# 201_ConnectionPart2-Part1.net
KiCad netlist of a schematic drawn in Altium Designer
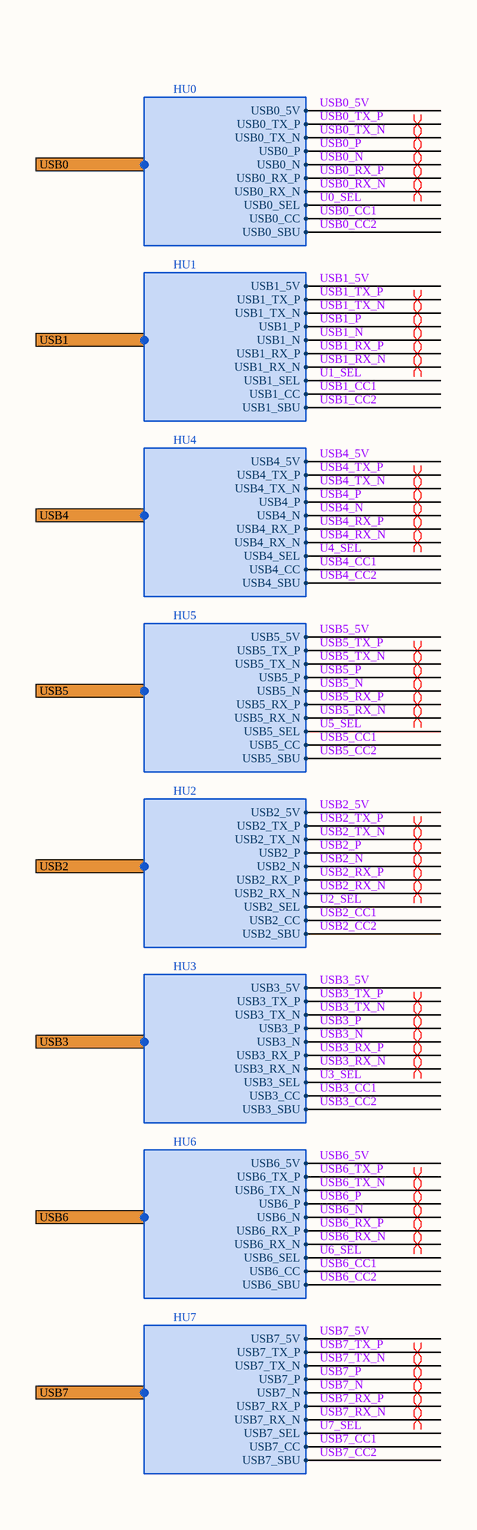
[diagram p0: 201_ConnectionPart2-Part1.SchDoc, left]
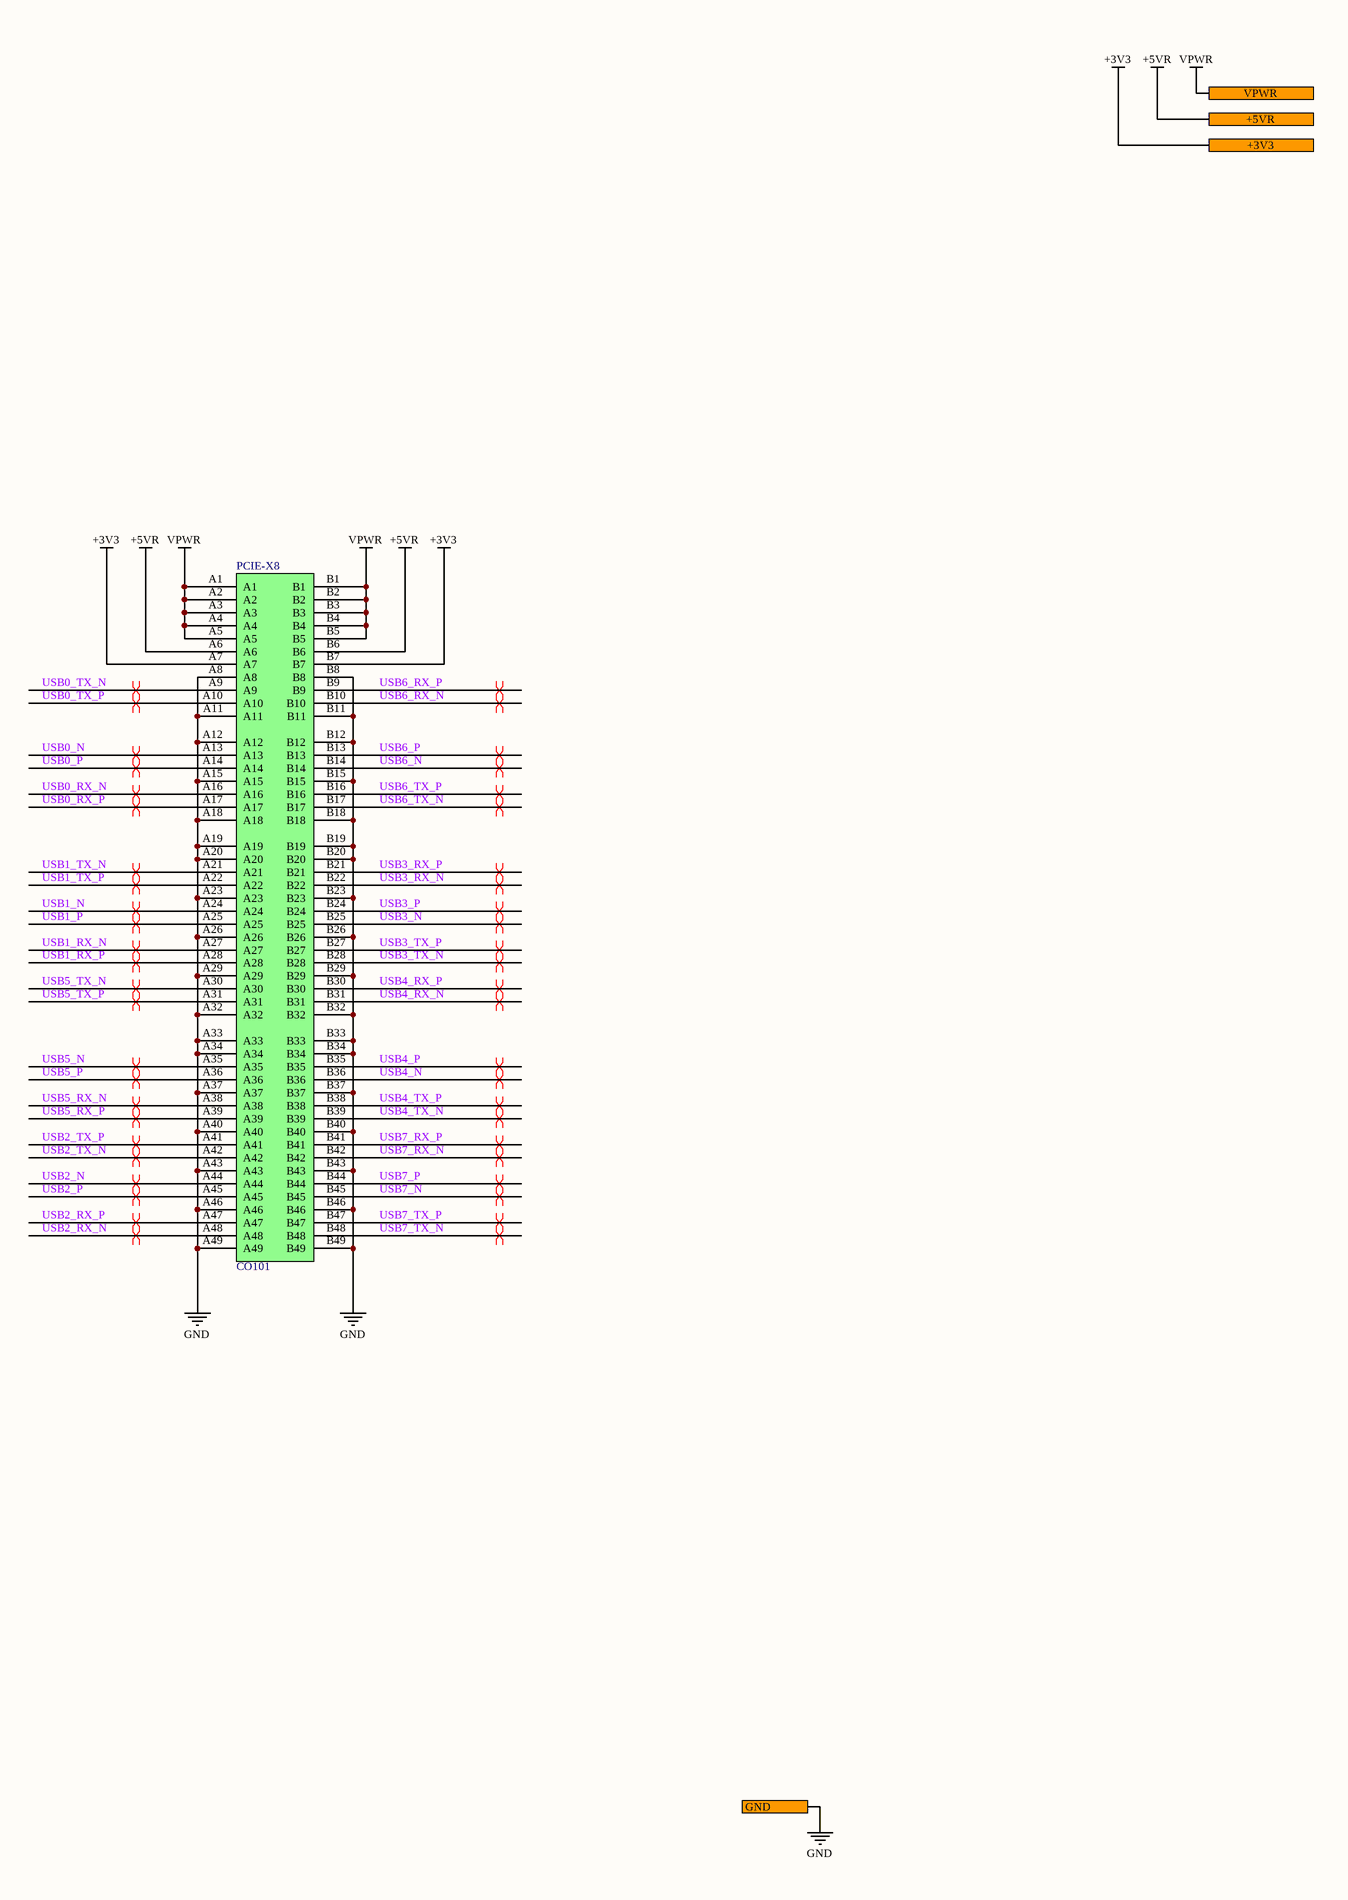
[diagram p1: 201_ConnectionPart2-Part1.SchDoc, right]

(export (version "E")
  (design (tool "Eeschema 10.0.6"))
  (components
    (comp (ref "CO101")
      (value "PCIE-X8")
      (footprint "PCIE-X8-PCB-BASIC")
      (description "PCIE GEN4-X8, Male")
      (fields (field (name "REFVAL") "PCIE-X8") (field (name "PART NUMBER") "CO0052"))
      (libsource (lib "GTS_Database") (part "PCIE-X8"))
    )
  )
  (nets
    (net (code "9") (name "+3V3") (class "Default")
      (node (ref "CO101") (pin "A7") (pinfunction "A7_A7") (pintype "passive"))
      (node (ref "CO101") (pin "B7") (pinfunction "B7_B7") (pintype "passive"))
    )
    (net (code "10") (name "+5VR") (class "Default")
      (node (ref "CO101") (pin "A6") (pinfunction "A6_A6") (pintype "passive"))
      (node (ref "CO101") (pin "B6") (pinfunction "B6_B6") (pintype "passive"))
    )
    (net (code "22") (name "/USB0_N") (class "Default")
      (node (ref "CO101") (pin "A13") (pinfunction "A13_A13") (pintype "passive"))
    )
    (net (code "23") (name "/USB0_P") (class "Default")
      (node (ref "CO101") (pin "A14") (pinfunction "A14_A14") (pintype "passive"))
    )
    (net (code "24") (name "/USB0_RX_N") (class "Default")
      (node (ref "CO101") (pin "A16") (pinfunction "A16_A16") (pintype "passive"))
    )
    (net (code "25") (name "/USB0_RX_P") (class "Default")
      (node (ref "CO101") (pin "A17") (pinfunction "A17_A17") (pintype "passive"))
    )
    (net (code "26") (name "/USB0_TX_N") (class "Default")
      (node (ref "CO101") (pin "A9") (pinfunction "A9_A9") (pintype "passive"))
    )
    (net (code "27") (name "/USB0_TX_P") (class "Default")
      (node (ref "CO101") (pin "A10") (pinfunction "A10_A10") (pintype "passive"))
    )
    (net (code "31") (name "/USB1_N") (class "Default")
      (node (ref "CO101") (pin "A24") (pinfunction "A24_A24") (pintype "passive"))
    )
    (net (code "32") (name "/USB1_P") (class "Default")
      (node (ref "CO101") (pin "A25") (pinfunction "A25_A25") (pintype "passive"))
    )
    (net (code "33") (name "/USB1_RX_N") (class "Default")
      (node (ref "CO101") (pin "A27") (pinfunction "A27_A27") (pintype "passive"))
    )
    (net (code "34") (name "/USB1_RX_P") (class "Default")
      (node (ref "CO101") (pin "A28") (pinfunction "A28_A28") (pintype "passive"))
    )
    (net (code "35") (name "/USB1_TX_N") (class "Default")
      (node (ref "CO101") (pin "A21") (pinfunction "A21_A21") (pintype "passive"))
    )
    (net (code "36") (name "/USB1_TX_P") (class "Default")
      (node (ref "CO101") (pin "A22") (pinfunction "A22_A22") (pintype "passive"))
    )
    (net (code "40") (name "/USB2_N") (class "Default")
      (node (ref "CO101") (pin "A44") (pinfunction "A44_A44") (pintype "passive"))
    )
    (net (code "41") (name "/USB2_P") (class "Default")
      (node (ref "CO101") (pin "A45") (pinfunction "A45_A45") (pintype "passive"))
    )
    (net (code "42") (name "/USB2_RX_N") (class "Default")
      (node (ref "CO101") (pin "A48") (pinfunction "A48_A48") (pintype "passive"))
    )
    (net (code "43") (name "/USB2_RX_P") (class "Default")
      (node (ref "CO101") (pin "A47") (pinfunction "A47_A47") (pintype "passive"))
    )
    (net (code "44") (name "/USB2_TX_N") (class "Default")
      (node (ref "CO101") (pin "A42") (pinfunction "A42_A42") (pintype "passive"))
    )
    (net (code "45") (name "/USB2_TX_P") (class "Default")
      (node (ref "CO101") (pin "A41") (pinfunction "A41_A41") (pintype "passive"))
    )
    (net (code "49") (name "/USB3_N") (class "Default")
      (node (ref "CO101") (pin "B25") (pinfunction "B25_B25") (pintype "passive"))
    )
    (net (code "50") (name "/USB3_P") (class "Default")
      (node (ref "CO101") (pin "B24") (pinfunction "B24_B24") (pintype "passive"))
    )
    (net (code "51") (name "/USB3_RX_N") (class "Default")
      (node (ref "CO101") (pin "B22") (pinfunction "B22_B22") (pintype "passive"))
    )
    (net (code "52") (name "/USB3_RX_P") (class "Default")
      (node (ref "CO101") (pin "B21") (pinfunction "B21_B21") (pintype "passive"))
    )
    (net (code "53") (name "/USB3_TX_N") (class "Default")
      (node (ref "CO101") (pin "B28") (pinfunction "B28_B28") (pintype "passive"))
    )
    (net (code "54") (name "/USB3_TX_P") (class "Default")
      (node (ref "CO101") (pin "B27") (pinfunction "B27_B27") (pintype "passive"))
    )
    (net (code "58") (name "/USB4_N") (class "Default")
      (node (ref "CO101") (pin "B36") (pinfunction "B36_B36") (pintype "passive"))
    )
    (net (code "59") (name "/USB4_P") (class "Default")
      (node (ref "CO101") (pin "B35") (pinfunction "B35_B35") (pintype "passive"))
    )
    (net (code "60") (name "/USB4_RX_N") (class "Default")
      (node (ref "CO101") (pin "B31") (pinfunction "B31_B31") (pintype "passive"))
    )
    (net (code "61") (name "/USB4_RX_P") (class "Default")
      (node (ref "CO101") (pin "B30") (pinfunction "B30_B30") (pintype "passive"))
    )
    (net (code "62") (name "/USB4_TX_N") (class "Default")
      (node (ref "CO101") (pin "B39") (pinfunction "B39_B39") (pintype "passive"))
    )
    (net (code "63") (name "/USB4_TX_P") (class "Default")
      (node (ref "CO101") (pin "B38") (pinfunction "B38_B38") (pintype "passive"))
    )
    (net (code "67") (name "/USB5_N") (class "Default")
      (node (ref "CO101") (pin "A35") (pinfunction "A35_A35") (pintype "passive"))
    )
    (net (code "68") (name "/USB5_P") (class "Default")
      (node (ref "CO101") (pin "A36") (pinfunction "A36_A36") (pintype "passive"))
    )
    (net (code "69") (name "/USB5_RX_N") (class "Default")
      (node (ref "CO101") (pin "A38") (pinfunction "A38_A38") (pintype "passive"))
    )
    (net (code "70") (name "/USB5_RX_P") (class "Default")
      (node (ref "CO101") (pin "A39") (pinfunction "A39_A39") (pintype "passive"))
    )
    (net (code "71") (name "/USB5_TX_N") (class "Default")
      (node (ref "CO101") (pin "A30") (pinfunction "A30_A30") (pintype "passive"))
    )
    (net (code "72") (name "/USB5_TX_P") (class "Default")
      (node (ref "CO101") (pin "A31") (pinfunction "A31_A31") (pintype "passive"))
    )
    (net (code "76") (name "/USB6_N") (class "Default")
      (node (ref "CO101") (pin "B14") (pinfunction "B14_B14") (pintype "passive"))
    )
    (net (code "77") (name "/USB6_P") (class "Default")
      (node (ref "CO101") (pin "B13") (pinfunction "B13_B13") (pintype "passive"))
    )
    (net (code "78") (name "/USB6_RX_N") (class "Default")
      (node (ref "CO101") (pin "B10") (pinfunction "B10_B10") (pintype "passive"))
    )
    (net (code "79") (name "/USB6_RX_P") (class "Default")
      (node (ref "CO101") (pin "B9") (pinfunction "B9_B9") (pintype "passive"))
    )
    (net (code "80") (name "/USB6_TX_N") (class "Default")
      (node (ref "CO101") (pin "B17") (pinfunction "B17_B17") (pintype "passive"))
    )
    (net (code "81") (name "/USB6_TX_P") (class "Default")
      (node (ref "CO101") (pin "B16") (pinfunction "B16_B16") (pintype "passive"))
    )
    (net (code "85") (name "/USB7_N") (class "Default")
      (node (ref "CO101") (pin "B45") (pinfunction "B45_B45") (pintype "passive"))
    )
    (net (code "86") (name "/USB7_P") (class "Default")
      (node (ref "CO101") (pin "B44") (pinfunction "B44_B44") (pintype "passive"))
    )
    (net (code "87") (name "/USB7_RX_N") (class "Default")
      (node (ref "CO101") (pin "B42") (pinfunction "B42_B42") (pintype "passive"))
    )
    (net (code "88") (name "/USB7_RX_P") (class "Default")
      (node (ref "CO101") (pin "B41") (pinfunction "B41_B41") (pintype "passive"))
    )
    (net (code "89") (name "/USB7_TX_N") (class "Default")
      (node (ref "CO101") (pin "B48") (pinfunction "B48_B48") (pintype "passive"))
    )
    (net (code "90") (name "/USB7_TX_P") (class "Default")
      (node (ref "CO101") (pin "B47") (pinfunction "B47_B47") (pintype "passive"))
    )
    (net (code "99") (name "GND") (class "Default")
      (node (ref "CO101") (pin "A11") (pinfunction "A11_A11") (pintype "passive"))
      (node (ref "CO101") (pin "A12") (pinfunction "A12_A12") (pintype "passive"))
      (node (ref "CO101") (pin "A15") (pinfunction "A15_A15") (pintype "passive"))
      (node (ref "CO101") (pin "A18") (pinfunction "A18_A18") (pintype "passive"))
      (node (ref "CO101") (pin "A19") (pinfunction "A19_A19") (pintype "passive"))
      (node (ref "CO101") (pin "A20") (pinfunction "A20_A20") (pintype "passive"))
      (node (ref "CO101") (pin "A23") (pinfunction "A23_A23") (pintype "passive"))
      (node (ref "CO101") (pin "A26") (pinfunction "A26_A26") (pintype "passive"))
      (node (ref "CO101") (pin "A29") (pinfunction "A29_A29") (pintype "passive"))
      (node (ref "CO101") (pin "A32") (pinfunction "A32_A32") (pintype "passive"))
      (node (ref "CO101") (pin "A33") (pinfunction "A33_A33") (pintype "passive"))
      (node (ref "CO101") (pin "A34") (pinfunction "A34_A34") (pintype "passive"))
      (node (ref "CO101") (pin "A37") (pinfunction "A37_A37") (pintype "passive"))
      (node (ref "CO101") (pin "A40") (pinfunction "A40_A40") (pintype "passive"))
      (node (ref "CO101") (pin "A43") (pinfunction "A43_A43") (pintype "passive"))
      (node (ref "CO101") (pin "A46") (pinfunction "A46_A46") (pintype "passive"))
      (node (ref "CO101") (pin "A49") (pinfunction "A49_A49") (pintype "passive"))
      (node (ref "CO101") (pin "A8") (pinfunction "A8_A8") (pintype "passive"))
      (node (ref "CO101") (pin "B11") (pinfunction "B11_B11") (pintype "passive"))
      (node (ref "CO101") (pin "B12") (pinfunction "B12_B12") (pintype "passive"))
      (node (ref "CO101") (pin "B15") (pinfunction "B15_B15") (pintype "passive"))
      (node (ref "CO101") (pin "B18") (pinfunction "B18_B18") (pintype "passive"))
      (node (ref "CO101") (pin "B19") (pinfunction "B19_B19") (pintype "passive"))
      (node (ref "CO101") (pin "B20") (pinfunction "B20_B20") (pintype "passive"))
      (node (ref "CO101") (pin "B23") (pinfunction "B23_B23") (pintype "passive"))
      (node (ref "CO101") (pin "B26") (pinfunction "B26_B26") (pintype "passive"))
      (node (ref "CO101") (pin "B29") (pinfunction "B29_B29") (pintype "passive"))
      (node (ref "CO101") (pin "B32") (pinfunction "B32_B32") (pintype "passive"))
      (node (ref "CO101") (pin "B33") (pinfunction "B33_B33") (pintype "passive"))
      (node (ref "CO101") (pin "B34") (pinfunction "B34_B34") (pintype "passive"))
      (node (ref "CO101") (pin "B37") (pinfunction "B37_B37") (pintype "passive"))
      (node (ref "CO101") (pin "B40") (pinfunction "B40_B40") (pintype "passive"))
      (node (ref "CO101") (pin "B43") (pinfunction "B43_B43") (pintype "passive"))
      (node (ref "CO101") (pin "B46") (pinfunction "B46_B46") (pintype "passive"))
      (node (ref "CO101") (pin "B49") (pinfunction "B49_B49") (pintype "passive"))
      (node (ref "CO101") (pin "B8") (pinfunction "B8_B8") (pintype "passive"))
    )
    (net (code "100") (name "VPWR") (class "Default")
      (node (ref "CO101") (pin "A1") (pinfunction "A1_A1") (pintype "passive"))
      (node (ref "CO101") (pin "A2") (pinfunction "A2_A2") (pintype "passive"))
      (node (ref "CO101") (pin "A3") (pinfunction "A3_A3") (pintype "passive"))
      (node (ref "CO101") (pin "A4") (pinfunction "A4_A4") (pintype "passive"))
      (node (ref "CO101") (pin "A5") (pinfunction "A5_A5") (pintype "passive"))
      (node (ref "CO101") (pin "B1") (pinfunction "B1_B1") (pintype "passive"))
      (node (ref "CO101") (pin "B2") (pinfunction "B2_B2") (pintype "passive"))
      (node (ref "CO101") (pin "B3") (pinfunction "B3_B3") (pintype "passive"))
      (node (ref "CO101") (pin "B4") (pinfunction "B4_B4") (pintype "passive"))
      (node (ref "CO101") (pin "B5") (pinfunction "B5_B5") (pintype "passive"))
    )
  )
)
